# 06-Front_Panel_SFP_2.net
KiCad netlist of a schematic drawn in Altium Designer
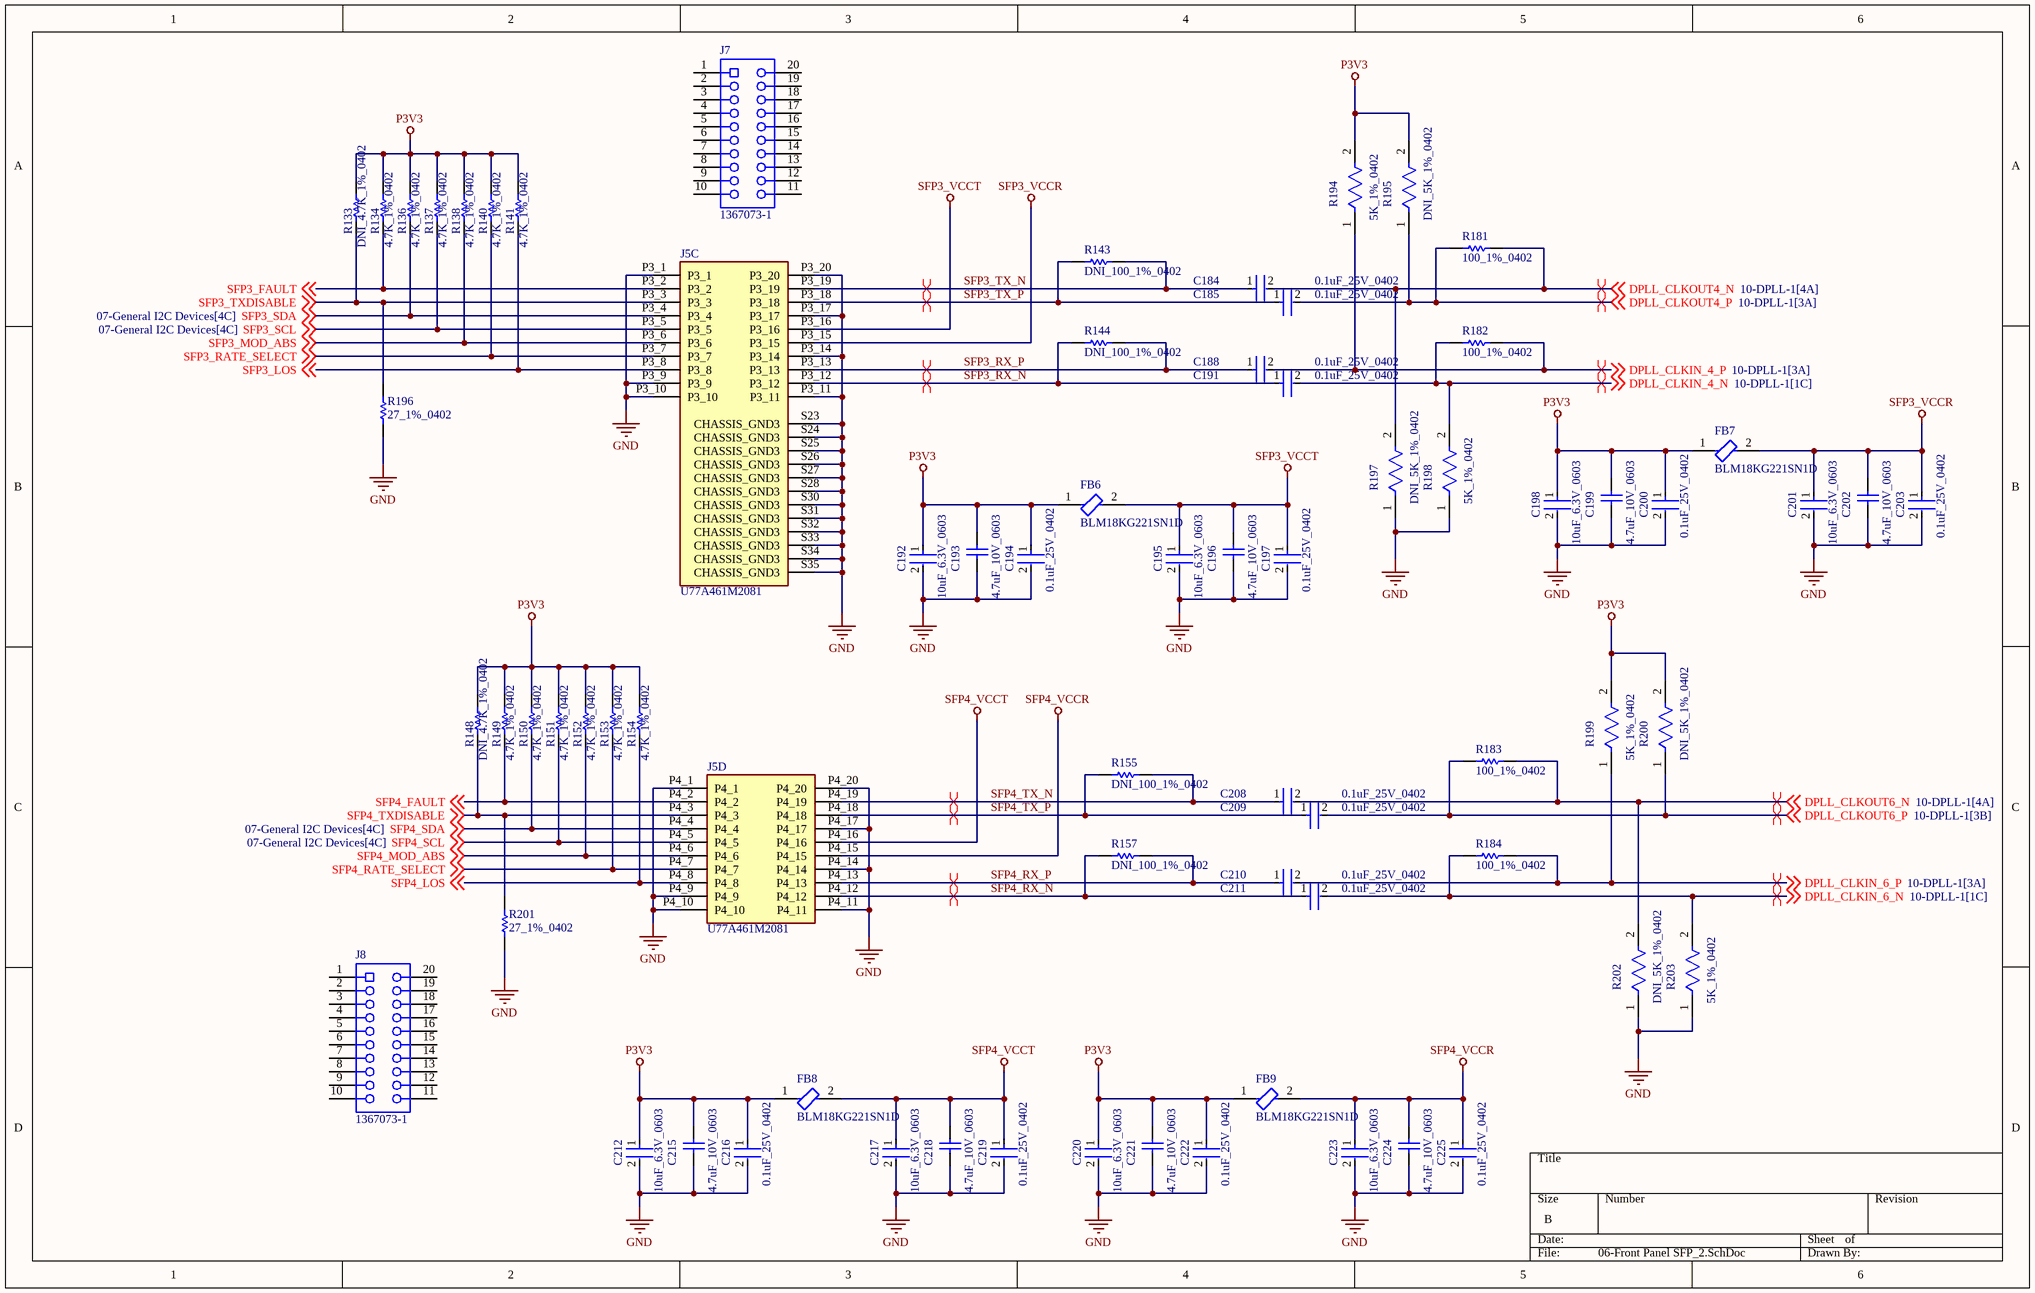
[diagram p0: 06-Front Panel SFP_2.SchDoc]

(export (version "E")
  (design (tool "Eeschema 10.0.6"))
  (components
    (comp (ref "C184")
      (value "0.1uF_25V_0402")
      (footprint "FP-0402-L_1_0_1-W_0_5_0_1-IPC_C")
      (description "General Purpose Ceramic Capacitor, 0402, 100nF, 10%, X7R, 15%, 25V")
      (fields (field (name "VOLTAGE") "25V") (field (name "TOLERANCE") "10%"))
      (libsource (lib "Altium Content Vault") (part "b4654b650e69147ec39a6b967a45e02"))
    )
    (comp (ref "C185")
      (value "0.1uF_25V_0402")
      (footprint "FP-0402-L_1_0_1-W_0_5_0_1-IPC_C")
      (description "General Purpose Ceramic Capacitor, 0402, 100nF, 10%, X7R, 15%, 25V")
      (fields (field (name "VOLTAGE") "25V") (field (name "TOLERANCE") "10%"))
      (libsource (lib "Altium Content Vault") (part "b4654b650e69147ec39a6b967a45e02"))
    )
    (comp (ref "C188")
      (value "0.1uF_25V_0402")
      (footprint "FP-0402-L_1_0_1-W_0_5_0_1-IPC_C")
      (description "General Purpose Ceramic Capacitor, 0402, 100nF, 10%, X7R, 15%, 25V")
      (fields (field (name "VOLTAGE") "25V") (field (name "TOLERANCE") "10%"))
      (libsource (lib "Altium Content Vault") (part "b4654b650e69147ec39a6b967a45e02"))
    )
    (comp (ref "C191")
      (value "0.1uF_25V_0402")
      (footprint "FP-0402-L_1_0_1-W_0_5_0_1-IPC_C")
      (description "General Purpose Ceramic Capacitor, 0402, 100nF, 10%, X7R, 15%, 25V")
      (fields (field (name "VOLTAGE") "25V") (field (name "TOLERANCE") "10%"))
      (libsource (lib "Altium Content Vault") (part "b4654b650e69147ec39a6b967a45e02"))
    )
    (comp (ref "C192")
      (value "10uF_6.3V_0603")
      (footprint "FP-C0603C106M9PACTU-MFG")
      (description "CAP CER 10UF 6.3V X5R 0603")
      (fields
        (field (name "MANUFACTURER PART NUMBER") "C0603C106M9PACTU")
        (field (name "MANUFACTURER") "Kemet")
      )
      (libsource (lib "Altium Content Vault") (part "b4654b650e69147ec39a6b967a45e02"))
    )
    (comp (ref "C193")
      (value "4.7uF_10V_0603")
      (footprint "CAPC1608X87X35NL15T15")
      (fields (field (name "PART NUMBER") "C0603C475K8PACTU") (field (name "MANUFACTURER") "Kemet"))
      (libsource (lib "Altium Content Vault") (part "CAP"))
    )
    (comp (ref "C194")
      (value "0.1uF_25V_0402")
      (footprint "FP-0402-L_1_0_1-W_0_5_0_1-IPC_C")
      (description "General Purpose Ceramic Capacitor, 0402, 100nF, 10%, X7R, 15%, 25V")
      (fields (field (name "VOLTAGE") "25V") (field (name "TOLERANCE") "10%"))
      (libsource (lib "Altium Content Vault") (part "b4654b650e69147ec39a6b967a45e02"))
    )
    (comp (ref "C195")
      (value "10uF_6.3V_0603")
      (footprint "FP-C0603C106M9PACTU-MFG")
      (description "CAP CER 10UF 6.3V X5R 0603")
      (fields
        (field (name "MANUFACTURER PART NUMBER") "C0603C106M9PACTU")
        (field (name "MANUFACTURER") "Kemet")
      )
      (libsource (lib "Altium Content Vault") (part "b4654b650e69147ec39a6b967a45e02"))
    )
    (comp (ref "C196")
      (value "4.7uF_10V_0603")
      (footprint "CAPC1608X87X35NL15T15")
      (fields (field (name "PART NUMBER") "C0603C475K8PACTU") (field (name "MANUFACTURER") "Kemet"))
      (libsource (lib "Altium Content Vault") (part "CAP"))
    )
    (comp (ref "C197")
      (value "0.1uF_25V_0402")
      (footprint "FP-0402-L_1_0_1-W_0_5_0_1-IPC_C")
      (description "General Purpose Ceramic Capacitor, 0402, 100nF, 10%, X7R, 15%, 25V")
      (fields (field (name "VOLTAGE") "25V") (field (name "TOLERANCE") "10%"))
      (libsource (lib "Altium Content Vault") (part "b4654b650e69147ec39a6b967a45e02"))
    )
    (comp (ref "C198")
      (value "10uF_6.3V_0603")
      (footprint "FP-C0603C106M9PACTU-MFG")
      (description "CAP CER 10UF 6.3V X5R 0603")
      (fields
        (field (name "MANUFACTURER PART NUMBER") "C0603C106M9PACTU")
        (field (name "MANUFACTURER") "Kemet")
      )
      (libsource (lib "Altium Content Vault") (part "b4654b650e69147ec39a6b967a45e02"))
    )
    (comp (ref "C199")
      (value "4.7uF_10V_0603")
      (footprint "CAPC1608X87X35NL15T15")
      (fields (field (name "PART NUMBER") "C0603C475K8PACTU") (field (name "MANUFACTURER") "Kemet"))
      (libsource (lib "Altium Content Vault") (part "CAP"))
    )
    (comp (ref "C200")
      (value "0.1uF_25V_0402")
      (footprint "FP-0402-L_1_0_1-W_0_5_0_1-IPC_C")
      (description "General Purpose Ceramic Capacitor, 0402, 100nF, 10%, X7R, 15%, 25V")
      (fields (field (name "VOLTAGE") "25V") (field (name "TOLERANCE") "10%"))
      (libsource (lib "Altium Content Vault") (part "b4654b650e69147ec39a6b967a45e02"))
    )
    (comp (ref "C201")
      (value "10uF_6.3V_0603")
      (footprint "FP-C0603C106M9PACTU-MFG")
      (description "CAP CER 10UF 6.3V X5R 0603")
      (fields
        (field (name "MANUFACTURER PART NUMBER") "C0603C106M9PACTU")
        (field (name "MANUFACTURER") "Kemet")
      )
      (libsource (lib "Altium Content Vault") (part "b4654b650e69147ec39a6b967a45e02"))
    )
    (comp (ref "C202")
      (value "4.7uF_10V_0603")
      (footprint "CAPC1608X87X35NL15T15")
      (fields (field (name "PART NUMBER") "C0603C475K8PACTU") (field (name "MANUFACTURER") "Kemet"))
      (libsource (lib "Altium Content Vault") (part "CAP"))
    )
    (comp (ref "C203")
      (value "0.1uF_25V_0402")
      (footprint "FP-0402-L_1_0_1-W_0_5_0_1-IPC_C")
      (description "General Purpose Ceramic Capacitor, 0402, 100nF, 10%, X7R, 15%, 25V")
      (fields (field (name "VOLTAGE") "25V") (field (name "TOLERANCE") "10%"))
      (libsource (lib "Altium Content Vault") (part "b4654b650e69147ec39a6b967a45e02"))
    )
    (comp (ref "C208")
      (value "0.1uF_25V_0402")
      (footprint "FP-0402-L_1_0_1-W_0_5_0_1-IPC_C")
      (description "General Purpose Ceramic Capacitor, 0402, 100nF, 10%, X7R, 15%, 25V")
      (fields (field (name "VOLTAGE") "25V") (field (name "TOLERANCE") "10%"))
      (libsource (lib "Altium Content Vault") (part "b4654b650e69147ec39a6b967a45e02"))
    )
    (comp (ref "C209")
      (value "0.1uF_25V_0402")
      (footprint "FP-0402-L_1_0_1-W_0_5_0_1-IPC_C")
      (description "General Purpose Ceramic Capacitor, 0402, 100nF, 10%, X7R, 15%, 25V")
      (fields (field (name "VOLTAGE") "25V") (field (name "TOLERANCE") "10%"))
      (libsource (lib "Altium Content Vault") (part "b4654b650e69147ec39a6b967a45e02"))
    )
    (comp (ref "C210")
      (value "0.1uF_25V_0402")
      (footprint "FP-0402-L_1_0_1-W_0_5_0_1-IPC_C")
      (description "General Purpose Ceramic Capacitor, 0402, 100nF, 10%, X7R, 15%, 25V")
      (fields (field (name "VOLTAGE") "25V") (field (name "TOLERANCE") "10%"))
      (libsource (lib "Altium Content Vault") (part "b4654b650e69147ec39a6b967a45e02"))
    )
    (comp (ref "C211")
      (value "0.1uF_25V_0402")
      (footprint "FP-0402-L_1_0_1-W_0_5_0_1-IPC_C")
      (description "General Purpose Ceramic Capacitor, 0402, 100nF, 10%, X7R, 15%, 25V")
      (fields (field (name "VOLTAGE") "25V") (field (name "TOLERANCE") "10%"))
      (libsource (lib "Altium Content Vault") (part "b4654b650e69147ec39a6b967a45e02"))
    )
    (comp (ref "C212")
      (value "10uF_6.3V_0603")
      (footprint "FP-C0603C106M9PACTU-MFG")
      (description "CAP CER 10UF 6.3V X5R 0603")
      (fields
        (field (name "MANUFACTURER PART NUMBER") "C0603C106M9PACTU")
        (field (name "MANUFACTURER") "Kemet")
      )
      (libsource (lib "Altium Content Vault") (part "b4654b650e69147ec39a6b967a45e02"))
    )
    (comp (ref "C215")
      (value "4.7uF_10V_0603")
      (footprint "CAPC1608X87X35NL15T15")
      (fields (field (name "PART NUMBER") "C0603C475K8PACTU") (field (name "MANUFACTURER") "Kemet"))
      (libsource (lib "Altium Content Vault") (part "CAP"))
    )
    (comp (ref "C216")
      (value "0.1uF_25V_0402")
      (footprint "FP-0402-L_1_0_1-W_0_5_0_1-IPC_C")
      (description "General Purpose Ceramic Capacitor, 0402, 100nF, 10%, X7R, 15%, 25V")
      (fields (field (name "VOLTAGE") "25V") (field (name "TOLERANCE") "10%"))
      (libsource (lib "Altium Content Vault") (part "b4654b650e69147ec39a6b967a45e02"))
    )
    (comp (ref "C217")
      (value "10uF_6.3V_0603")
      (footprint "FP-C0603C106M9PACTU-MFG")
      (description "CAP CER 10UF 6.3V X5R 0603")
      (fields
        (field (name "MANUFACTURER PART NUMBER") "C0603C106M9PACTU")
        (field (name "MANUFACTURER") "Kemet")
      )
      (libsource (lib "Altium Content Vault") (part "b4654b650e69147ec39a6b967a45e02"))
    )
    (comp (ref "C218")
      (value "4.7uF_10V_0603")
      (footprint "CAPC1608X87X35NL15T15")
      (fields (field (name "PART NUMBER") "C0603C475K8PACTU") (field (name "MANUFACTURER") "Kemet"))
      (libsource (lib "Altium Content Vault") (part "CAP"))
    )
    (comp (ref "C219")
      (value "0.1uF_25V_0402")
      (footprint "FP-0402-L_1_0_1-W_0_5_0_1-IPC_C")
      (description "General Purpose Ceramic Capacitor, 0402, 100nF, 10%, X7R, 15%, 25V")
      (fields (field (name "VOLTAGE") "25V") (field (name "TOLERANCE") "10%"))
      (libsource (lib "Altium Content Vault") (part "b4654b650e69147ec39a6b967a45e02"))
    )
    (comp (ref "C220")
      (value "10uF_6.3V_0603")
      (footprint "FP-C0603C106M9PACTU-MFG")
      (description "CAP CER 10UF 6.3V X5R 0603")
      (fields
        (field (name "MANUFACTURER PART NUMBER") "C0603C106M9PACTU")
        (field (name "MANUFACTURER") "Kemet")
      )
      (libsource (lib "Altium Content Vault") (part "b4654b650e69147ec39a6b967a45e02"))
    )
    (comp (ref "C221")
      (value "4.7uF_10V_0603")
      (footprint "CAPC1608X87X35NL15T15")
      (fields (field (name "PART NUMBER") "C0603C475K8PACTU") (field (name "MANUFACTURER") "Kemet"))
      (libsource (lib "Altium Content Vault") (part "CAP"))
    )
    (comp (ref "C222")
      (value "0.1uF_25V_0402")
      (footprint "FP-0402-L_1_0_1-W_0_5_0_1-IPC_C")
      (description "General Purpose Ceramic Capacitor, 0402, 100nF, 10%, X7R, 15%, 25V")
      (fields (field (name "VOLTAGE") "25V") (field (name "TOLERANCE") "10%"))
      (libsource (lib "Altium Content Vault") (part "b4654b650e69147ec39a6b967a45e02"))
    )
    (comp (ref "C223")
      (value "10uF_6.3V_0603")
      (footprint "FP-C0603C106M9PACTU-MFG")
      (description "CAP CER 10UF 6.3V X5R 0603")
      (fields
        (field (name "MANUFACTURER PART NUMBER") "C0603C106M9PACTU")
        (field (name "MANUFACTURER") "Kemet")
      )
      (libsource (lib "Altium Content Vault") (part "b4654b650e69147ec39a6b967a45e02"))
    )
    (comp (ref "C224")
      (value "4.7uF_10V_0603")
      (footprint "CAPC1608X87X35NL15T15")
      (fields (field (name "PART NUMBER") "C0603C475K8PACTU") (field (name "MANUFACTURER") "Kemet"))
      (libsource (lib "Altium Content Vault") (part "CAP"))
    )
    (comp (ref "C225")
      (value "0.1uF_25V_0402")
      (footprint "FP-0402-L_1_0_1-W_0_5_0_1-IPC_C")
      (description "General Purpose Ceramic Capacitor, 0402, 100nF, 10%, X7R, 15%, 25V")
      (fields (field (name "VOLTAGE") "25V") (field (name "TOLERANCE") "10%"))
      (libsource (lib "Altium Content Vault") (part "b4654b650e69147ec39a6b967a45e02"))
    )
    (comp (ref "FB6")
      (value "BLM18KG221SN1D")
      (footprint "FP-BLM18-0_15-t0_8-IPC_B")
      (description "Chip Ferrite Bead, 0603, 220Ω @ 100MHz, 0.05Ω, 25%, 2.2A")
      (fields (field (name "TOLERANCE") "25%"))
      (libsource (lib "Altium Content Vault") (part "5f30dd21d616792df468990f7003faa"))
    )
    (comp (ref "FB7")
      (value "BLM18KG221SN1D")
      (footprint "FP-BLM18-0_15-t0_8-IPC_B")
      (description "Chip Ferrite Bead, 0603, 220Ω @ 100MHz, 0.05Ω, 25%, 2.2A")
      (fields (field (name "TOLERANCE") "25%"))
      (libsource (lib "Altium Content Vault") (part "5f30dd21d616792df468990f7003faa"))
    )
    (comp (ref "FB8")
      (value "BLM18KG221SN1D")
      (footprint "FP-BLM18-0_15-t0_8-IPC_B")
      (description "Chip Ferrite Bead, 0603, 220Ω @ 100MHz, 0.05Ω, 25%, 2.2A")
      (fields (field (name "TOLERANCE") "25%"))
      (libsource (lib "Altium Content Vault") (part "5f30dd21d616792df468990f7003faa"))
    )
    (comp (ref "FB9")
      (value "BLM18KG221SN1D")
      (footprint "FP-BLM18-0_15-t0_8-IPC_B")
      (description "Chip Ferrite Bead, 0603, 220Ω @ 100MHz, 0.05Ω, 25%, 2.2A")
      (fields (field (name "TOLERANCE") "25%"))
      (libsource (lib "Altium Content Vault") (part "5f30dd21d616792df468990f7003faa"))
    )
    (comp (ref "J5")
      (value "U77A461M2081")
      (footprint "AMPHENOL_U77A461M2081")
      (fields (field (name "MF") "AMPHENOL ICC / FCI"))
      (libsource (lib "U77A461M2081") (part "U77A461M2081"))
    )
    (comp (ref "J7")
      (value "1367073-1")
      (footprint "TECO-1367073-1_V")
      (fields (field (name "MANUFACTURER") "TE Connectivity"))
      (libsource (lib "Altium Content Vault") (part "CN-2P-F-R20_B"))
    )
    (comp (ref "J8")
      (value "1367073-1")
      (footprint "TECO-1367073-1_V")
      (fields (field (name "MANUFACTURER") "TE Connectivity"))
      (libsource (lib "Altium Content Vault") (part "CN-2P-F-R20_B"))
    )
    (comp (ref "R133")
      (value "DNI_4.7K_1%_0402")
      (footprint "RESC1005X40X25NL10T10")
      (fields (field (name "MANUFACTURER") "Bourns") (field (name "PART NUMBER") "CR0402-FX-4701GLF"))
      (libsource (lib "Altium Content Vault") (part "RES"))
    )
    (comp (ref "R134")
      (value "4.7K_1%_0402")
      (footprint "RESC1005X40X25NL10T10")
      (fields (field (name "MANUFACTURER") "Bourns") (field (name "PART NUMBER") "CR0402-FX-4701GLF"))
      (libsource (lib "Altium Content Vault") (part "RES"))
    )
    (comp (ref "R136")
      (value "4.7K_1%_0402")
      (footprint "RESC1005X40X25NL10T10")
      (fields (field (name "MANUFACTURER") "Bourns") (field (name "PART NUMBER") "CR0402-FX-4701GLF"))
      (libsource (lib "Altium Content Vault") (part "RES"))
    )
    (comp (ref "R137")
      (value "4.7K_1%_0402")
      (footprint "RESC1005X40X25NL10T10")
      (fields (field (name "MANUFACTURER") "Bourns") (field (name "PART NUMBER") "CR0402-FX-4701GLF"))
      (libsource (lib "Altium Content Vault") (part "RES"))
    )
    (comp (ref "R138")
      (value "4.7K_1%_0402")
      (footprint "RESC1005X40X25NL10T10")
      (fields (field (name "MANUFACTURER") "Bourns") (field (name "PART NUMBER") "CR0402-FX-4701GLF"))
      (libsource (lib "Altium Content Vault") (part "RES"))
    )
    (comp (ref "R140")
      (value "4.7K_1%_0402")
      (footprint "RESC1005X40X25NL10T10")
      (fields (field (name "MANUFACTURER") "Bourns") (field (name "PART NUMBER") "CR0402-FX-4701GLF"))
      (libsource (lib "Altium Content Vault") (part "RES"))
    )
    (comp (ref "R141")
      (value "4.7K_1%_0402")
      (footprint "RESC1005X40X25NL10T10")
      (fields (field (name "MANUFACTURER") "Bourns") (field (name "PART NUMBER") "CR0402-FX-4701GLF"))
      (libsource (lib "Altium Content Vault") (part "RES"))
    )
    (comp (ref "R143")
      (value "DNI_100_1%_0402")
      (footprint "RESC1005X40X25NL05T10")
      (fields (field (name "MANUFACTURER") "Yageo") (field (name "PART NUMBER") "RC0402FR-13100RL"))
      (libsource (lib "Altium Content Vault") (part "RES"))
    )
    (comp (ref "R144")
      (value "DNI_100_1%_0402")
      (footprint "RESC1005X40X25NL05T10")
      (fields (field (name "MANUFACTURER") "Yageo") (field (name "PART NUMBER") "RC0402FR-13100RL"))
      (libsource (lib "Altium Content Vault") (part "RES"))
    )
    (comp (ref "R148")
      (value "DNI_4.7K_1%_0402")
      (footprint "RESC1005X40X25NL10T10")
      (fields (field (name "MANUFACTURER") "Bourns") (field (name "PART NUMBER") "CR0402-FX-4701GLF"))
      (libsource (lib "Altium Content Vault") (part "RES"))
    )
    (comp (ref "R149")
      (value "4.7K_1%_0402")
      (footprint "RESC1005X40X25NL10T10")
      (fields (field (name "MANUFACTURER") "Bourns") (field (name "PART NUMBER") "CR0402-FX-4701GLF"))
      (libsource (lib "Altium Content Vault") (part "RES"))
    )
    (comp (ref "R150")
      (value "4.7K_1%_0402")
      (footprint "RESC1005X40X25NL10T10")
      (fields (field (name "MANUFACTURER") "Bourns") (field (name "PART NUMBER") "CR0402-FX-4701GLF"))
      (libsource (lib "Altium Content Vault") (part "RES"))
    )
    (comp (ref "R151")
      (value "4.7K_1%_0402")
      (footprint "RESC1005X40X25NL10T10")
      (fields (field (name "MANUFACTURER") "Bourns") (field (name "PART NUMBER") "CR0402-FX-4701GLF"))
      (libsource (lib "Altium Content Vault") (part "RES"))
    )
    (comp (ref "R152")
      (value "4.7K_1%_0402")
      (footprint "RESC1005X40X25NL10T10")
      (fields (field (name "MANUFACTURER") "Bourns") (field (name "PART NUMBER") "CR0402-FX-4701GLF"))
      (libsource (lib "Altium Content Vault") (part "RES"))
    )
    (comp (ref "R153")
      (value "4.7K_1%_0402")
      (footprint "RESC1005X40X25NL10T10")
      (fields (field (name "MANUFACTURER") "Bourns") (field (name "PART NUMBER") "CR0402-FX-4701GLF"))
      (libsource (lib "Altium Content Vault") (part "RES"))
    )
    (comp (ref "R154")
      (value "4.7K_1%_0402")
      (footprint "RESC1005X40X25NL10T10")
      (fields (field (name "MANUFACTURER") "Bourns") (field (name "PART NUMBER") "CR0402-FX-4701GLF"))
      (libsource (lib "Altium Content Vault") (part "RES"))
    )
    (comp (ref "R155")
      (value "DNI_100_1%_0402")
      (footprint "RESC1005X40X25NL05T10")
      (fields (field (name "MANUFACTURER") "Yageo") (field (name "PART NUMBER") "RC0402FR-13100RL"))
      (libsource (lib "Altium Content Vault") (part "RES"))
    )
    (comp (ref "R157")
      (value "DNI_100_1%_0402")
      (footprint "RESC1005X40X25NL05T10")
      (fields (field (name "MANUFACTURER") "Yageo") (field (name "PART NUMBER") "RC0402FR-13100RL"))
      (libsource (lib "Altium Content Vault") (part "RES"))
    )
    (comp (ref "R181")
      (value "100_1%_0402")
      (footprint "RESC1005X40X25NL05T10")
      (fields (field (name "MANUFACTURER") "Yageo") (field (name "PART NUMBER") "RC0402FR-13100RL"))
      (libsource (lib "Altium Content Vault") (part "RES"))
    )
    (comp (ref "R182")
      (value "100_1%_0402")
      (footprint "RESC1005X40X25NL05T10")
      (fields (field (name "MANUFACTURER") "Yageo") (field (name "PART NUMBER") "RC0402FR-13100RL"))
      (libsource (lib "Altium Content Vault") (part "RES"))
    )
    (comp (ref "R183")
      (value "100_1%_0402")
      (footprint "RESC1005X40X25NL05T10")
      (fields (field (name "MANUFACTURER") "Yageo") (field (name "PART NUMBER") "RC0402FR-13100RL"))
      (libsource (lib "Altium Content Vault") (part "RES"))
    )
    (comp (ref "R184")
      (value "100_1%_0402")
      (footprint "RESC1005X40X25NL05T10")
      (fields (field (name "MANUFACTURER") "Yageo") (field (name "PART NUMBER") "RC0402FR-13100RL"))
      (libsource (lib "Altium Content Vault") (part "RES"))
    )
    (comp (ref "R194")
      (value "5K_1%_0402")
      (footprint "FP-RC0402-MFG")
      (description "RES SMD 5K OHM 1% 1/16W 0402")
      (fields (field (name "MANUFACTURER") "Yageo") (field (name "TOLERANCE") "1%"))
      (libsource (lib "Altium Content Vault") (part "1029c3af85768c4190bb7ad29bc67b5"))
    )
    (comp (ref "R195")
      (value "DNI_5K_1%_0402")
      (footprint "FP-RC0402-MFG")
      (description "RES SMD 5K OHM 1% 1/16W 0402")
      (fields (field (name "MANUFACTURER") "Yageo") (field (name "TOLERANCE") "1%"))
      (libsource (lib "Altium Content Vault") (part "1029c3af85768c4190bb7ad29bc67b5"))
    )
    (comp (ref "R196")
      (value "27_1%_0402")
      (footprint "RESC1005X40X25NL05T05")
      (fields (field (name "PART NUMBER") "CRCW040227R0FKED") (field (name "MANUFACTURER") "Vishay Dale"))
      (libsource (lib "Altium Content Vault") (part "RES"))
    )
    (comp (ref "R197")
      (value "DNI_5K_1%_0402")
      (footprint "FP-RC0402-MFG")
      (description "RES SMD 5K OHM 1% 1/16W 0402")
      (fields (field (name "MANUFACTURER") "Yageo") (field (name "TOLERANCE") "1%"))
      (libsource (lib "Altium Content Vault") (part "1029c3af85768c4190bb7ad29bc67b5"))
    )
    (comp (ref "R198")
      (value "5K_1%_0402")
      (footprint "FP-RC0402-MFG")
      (description "RES SMD 5K OHM 1% 1/16W 0402")
      (fields (field (name "MANUFACTURER") "Yageo") (field (name "TOLERANCE") "1%"))
      (libsource (lib "Altium Content Vault") (part "1029c3af85768c4190bb7ad29bc67b5"))
    )
    (comp (ref "R199")
      (value "5K_1%_0402")
      (footprint "FP-RC0402-MFG")
      (description "RES SMD 5K OHM 1% 1/16W 0402")
      (fields (field (name "MANUFACTURER") "Yageo") (field (name "TOLERANCE") "1%"))
      (libsource (lib "Altium Content Vault") (part "1029c3af85768c4190bb7ad29bc67b5"))
    )
    (comp (ref "R200")
      (value "DNI_5K_1%_0402")
      (footprint "FP-RC0402-MFG")
      (description "RES SMD 5K OHM 1% 1/16W 0402")
      (fields (field (name "MANUFACTURER") "Yageo") (field (name "TOLERANCE") "1%"))
      (libsource (lib "Altium Content Vault") (part "1029c3af85768c4190bb7ad29bc67b5"))
    )
    (comp (ref "R201")
      (value "27_1%_0402")
      (footprint "RESC1005X40X25NL05T05")
      (fields (field (name "PART NUMBER") "CRCW040227R0FKED") (field (name "MANUFACTURER") "Vishay Dale"))
      (libsource (lib "Altium Content Vault") (part "RES"))
    )
    (comp (ref "R202")
      (value "DNI_5K_1%_0402")
      (footprint "FP-RC0402-MFG")
      (description "RES SMD 5K OHM 1% 1/16W 0402")
      (fields (field (name "MANUFACTURER") "Yageo") (field (name "TOLERANCE") "1%"))
      (libsource (lib "Altium Content Vault") (part "1029c3af85768c4190bb7ad29bc67b5"))
    )
    (comp (ref "R203")
      (value "5K_1%_0402")
      (footprint "FP-RC0402-MFG")
      (description "RES SMD 5K OHM 1% 1/16W 0402")
      (fields (field (name "MANUFACTURER") "Yageo") (field (name "TOLERANCE") "1%"))
      (libsource (lib "Altium Content Vault") (part "1029c3af85768c4190bb7ad29bc67b5"))
    )
  )
  (nets
    (net (code "1") (name "/SFP3_RX_N") (class "Default")
      (node (ref "C191") (pin "1") (pinfunction "1_1") (pintype "passive"))
      (node (ref "J5") (pin "P3_12") (pinfunction "P3_12_P3_12") (pintype "passive"))
      (node (ref "R144") (pin "1") (pinfunction "1_1") (pintype "passive"))
    )
    (net (code "2") (name "/SFP3_RX_P") (class "Default")
      (node (ref "C188") (pin "1") (pinfunction "1_1") (pintype "passive"))
      (node (ref "J5") (pin "P3_13") (pinfunction "P3_13_P3_13") (pintype "passive"))
      (node (ref "R144") (pin "2") (pinfunction "2_2") (pintype "passive"))
    )
    (net (code "3") (name "/SFP3_TX_N") (class "Default")
      (node (ref "C184") (pin "1") (pinfunction "1_1") (pintype "passive"))
      (node (ref "J5") (pin "P3_19") (pinfunction "P3_19_P3_19") (pintype "passive"))
      (node (ref "R143") (pin "2") (pinfunction "2_2") (pintype "passive"))
    )
    (net (code "4") (name "/SFP3_TX_P") (class "Default")
      (node (ref "C185") (pin "1") (pinfunction "1_1") (pintype "passive"))
      (node (ref "J5") (pin "P3_18") (pinfunction "P3_18_P3_18") (pintype "passive"))
      (node (ref "R143") (pin "1") (pinfunction "1_1") (pintype "passive"))
    )
    (net (code "5") (name "/SFP4_RX_N") (class "Default")
      (node (ref "C211") (pin "1") (pinfunction "1_1") (pintype "passive"))
      (node (ref "J5") (pin "P4_12") (pinfunction "P4_12_P4_12") (pintype "passive"))
      (node (ref "R157") (pin "1") (pinfunction "1_1") (pintype "passive"))
    )
    (net (code "6") (name "/SFP4_RX_P") (class "Default")
      (node (ref "C210") (pin "1") (pinfunction "1_1") (pintype "passive"))
      (node (ref "J5") (pin "P4_13") (pinfunction "P4_13_P4_13") (pintype "passive"))
      (node (ref "R157") (pin "2") (pinfunction "2_2") (pintype "passive"))
    )
    (net (code "7") (name "/SFP4_TX_N") (class "Default")
      (node (ref "C208") (pin "1") (pinfunction "1_1") (pintype "passive"))
      (node (ref "J5") (pin "P4_19") (pinfunction "P4_19_P4_19") (pintype "passive"))
      (node (ref "R155") (pin "2") (pinfunction "2_2") (pintype "passive"))
    )
    (net (code "8") (name "/SFP4_TX_P") (class "Default")
      (node (ref "C209") (pin "1") (pinfunction "1_1") (pintype "passive"))
      (node (ref "J5") (pin "P4_18") (pinfunction "P4_18_P4_18") (pintype "passive"))
      (node (ref "R155") (pin "1") (pinfunction "1_1") (pintype "passive"))
    )
    (net (code "9") (name "DPLL_CLKIN_4_N") (class "Default")
      (node (ref "C191") (pin "2") (pinfunction "2_2") (pintype "passive"))
      (node (ref "R182") (pin "1") (pinfunction "1_1") (pintype "passive"))
      (node (ref "R198") (pin "2") (pinfunction "2_2") (pintype "passive"))
    )
    (net (code "10") (name "DPLL_CLKIN_4_P") (class "Default")
      (node (ref "C188") (pin "2") (pinfunction "2_2") (pintype "passive"))
      (node (ref "R182") (pin "2") (pinfunction "2_2") (pintype "passive"))
      (node (ref "R194") (pin "1") (pinfunction "1_1") (pintype "passive"))
    )
    (net (code "11") (name "DPLL_CLKIN_6_N") (class "Default")
      (node (ref "C211") (pin "2") (pinfunction "2_2") (pintype "passive"))
      (node (ref "R184") (pin "1") (pinfunction "1_1") (pintype "passive"))
      (node (ref "R203") (pin "2") (pinfunction "2_2") (pintype "passive"))
    )
    (net (code "12") (name "DPLL_CLKIN_6_P") (class "Default")
      (node (ref "C210") (pin "2") (pinfunction "2_2") (pintype "passive"))
      (node (ref "R184") (pin "2") (pinfunction "2_2") (pintype "passive"))
      (node (ref "R199") (pin "1") (pinfunction "1_1") (pintype "passive"))
    )
    (net (code "13") (name "DPLL_CLKOUT4_N") (class "Default")
      (node (ref "C184") (pin "2") (pinfunction "2_2") (pintype "passive"))
      (node (ref "R181") (pin "2") (pinfunction "2_2") (pintype "passive"))
      (node (ref "R197") (pin "2") (pinfunction "2_2") (pintype "passive"))
    )
    (net (code "14") (name "DPLL_CLKOUT4_P") (class "Default")
      (node (ref "C185") (pin "2") (pinfunction "2_2") (pintype "passive"))
      (node (ref "R181") (pin "1") (pinfunction "1_1") (pintype "passive"))
      (node (ref "R195") (pin "1") (pinfunction "1_1") (pintype "passive"))
    )
    (net (code "15") (name "DPLL_CLKOUT6_N") (class "Default")
      (node (ref "C208") (pin "2") (pinfunction "2_2") (pintype "passive"))
      (node (ref "R183") (pin "2") (pinfunction "2_2") (pintype "passive"))
      (node (ref "R202") (pin "2") (pinfunction "2_2") (pintype "passive"))
    )
    (net (code "16") (name "DPLL_CLKOUT6_P") (class "Default")
      (node (ref "C209") (pin "2") (pinfunction "2_2") (pintype "passive"))
      (node (ref "R183") (pin "1") (pinfunction "1_1") (pintype "passive"))
      (node (ref "R200") (pin "1") (pinfunction "1_1") (pintype "passive"))
    )
    (net (code "17") (name "GND") (class "Default")
      (node (ref "C192") (pin "2") (pinfunction "2_2") (pintype "passive"))
      (node (ref "C193") (pin "1") (pinfunction "1_1") (pintype "passive"))
      (node (ref "C194") (pin "2") (pinfunction "2_2") (pintype "passive"))
      (node (ref "C195") (pin "2") (pinfunction "2_2") (pintype "passive"))
      (node (ref "C196") (pin "1") (pinfunction "1_1") (pintype "passive"))
      (node (ref "C197") (pin "2") (pinfunction "2_2") (pintype "passive"))
      (node (ref "C198") (pin "2") (pinfunction "2_2") (pintype "passive"))
      (node (ref "C199") (pin "1") (pinfunction "1_1") (pintype "passive"))
      (node (ref "C200") (pin "2") (pinfunction "2_2") (pintype "passive"))
      (node (ref "C201") (pin "2") (pinfunction "2_2") (pintype "passive"))
      (node (ref "C202") (pin "1") (pinfunction "1_1") (pintype "passive"))
      (node (ref "C203") (pin "2") (pinfunction "2_2") (pintype "passive"))
      (node (ref "C212") (pin "2") (pinfunction "2_2") (pintype "passive"))
      (node (ref "C215") (pin "1") (pinfunction "1_1") (pintype "passive"))
      (node (ref "C216") (pin "2") (pinfunction "2_2") (pintype "passive"))
      (node (ref "C217") (pin "2") (pinfunction "2_2") (pintype "passive"))
      (node (ref "C218") (pin "1") (pinfunction "1_1") (pintype "passive"))
      (node (ref "C219") (pin "2") (pinfunction "2_2") (pintype "passive"))
      (node (ref "C220") (pin "2") (pinfunction "2_2") (pintype "passive"))
      (node (ref "C221") (pin "1") (pinfunction "1_1") (pintype "passive"))
      (node (ref "C222") (pin "2") (pinfunction "2_2") (pintype "passive"))
      (node (ref "C223") (pin "2") (pinfunction "2_2") (pintype "passive"))
      (node (ref "C224") (pin "1") (pinfunction "1_1") (pintype "passive"))
      (node (ref "C225") (pin "2") (pinfunction "2_2") (pintype "passive"))
      (node (ref "J5") (pin "P3_1") (pinfunction "P3_1_P3_1") (pintype "passive"))
      (node (ref "J5") (pin "P3_10") (pinfunction "P3_10_P3_10") (pintype "passive"))
      (node (ref "J5") (pin "P3_11") (pinfunction "P3_11_P3_11") (pintype "passive"))
      (node (ref "J5") (pin "P3_14") (pinfunction "P3_14_P3_14") (pintype "passive"))
      (node (ref "J5") (pin "P3_17") (pinfunction "P3_17_P3_17") (pintype "passive"))
      (node (ref "J5") (pin "P3_20") (pinfunction "P3_20_P3_20") (pintype "passive"))
      (node (ref "J5") (pin "P3_9") (pinfunction "P3_9_P3_9") (pintype "passive"))
      (node (ref "J5") (pin "P4_1") (pinfunction "P4_1_P4_1") (pintype "passive"))
      (node (ref "J5") (pin "P4_10") (pinfunction "P4_10_P4_10") (pintype "passive"))
      (node (ref "J5") (pin "P4_11") (pinfunction "P4_11_P4_11") (pintype "passive"))
      (node (ref "J5") (pin "P4_14") (pinfunction "P4_14_P4_14") (pintype "passive"))
      (node (ref "J5") (pin "P4_17") (pinfunction "P4_17_P4_17") (pintype "passive"))
      (node (ref "J5") (pin "P4_20") (pinfunction "P4_20_P4_20") (pintype "passive"))
      (node (ref "J5") (pin "P4_9") (pinfunction "P4_9_P4_9") (pintype "passive"))
      (node (ref "J5") (pin "S23") (pinfunction "CHASSIS_GND3_S23") (pintype "passive"))
      (node (ref "J5") (pin "S24") (pinfunction "CHASSIS_GND3_S24") (pintype "passive"))
      (node (ref "J5") (pin "S25") (pinfunction "CHASSIS_GND3_S25") (pintype "passive"))
      (node (ref "J5") (pin "S26") (pinfunction "CHASSIS_GND3_S26") (pintype "passive"))
      (node (ref "J5") (pin "S27") (pinfunction "CHASSIS_GND3_S27") (pintype "passive"))
      (node (ref "J5") (pin "S28") (pinfunction "CHASSIS_GND3_S28") (pintype "passive"))
      (node (ref "J5") (pin "S30") (pinfunction "CHASSIS_GND3_S30") (pintype "passive"))
      (node (ref "J5") (pin "S31") (pinfunction "CHASSIS_GND3_S31") (pintype "passive"))
      (node (ref "J5") (pin "S32") (pinfunction "CHASSIS_GND3_S32") (pintype "passive"))
      (node (ref "J5") (pin "S33") (pinfunction "CHASSIS_GND3_S33") (pintype "passive"))
      (node (ref "J5") (pin "S34") (pinfunction "CHASSIS_GND3_S34") (pintype "passive"))
      (node (ref "J5") (pin "S35") (pinfunction "CHASSIS_GND3_S35") (pintype "passive"))
      (node (ref "R196") (pin "1") (pinfunction "1_1") (pintype "passive"))
      (node (ref "R197") (pin "1") (pinfunction "1_1") (pintype "passive"))
      (node (ref "R198") (pin "1") (pinfunction "1_1") (pintype "passive"))
      (node (ref "R201") (pin "1") (pinfunction "1_1") (pintype "passive"))
      (node (ref "R202") (pin "1") (pinfunction "1_1") (pintype "passive"))
      (node (ref "R203") (pin "1") (pinfunction "1_1") (pintype "passive"))
    )
    (net (code "18") (name "P3V3") (class "Default")
      (node (ref "C192") (pin "1") (pinfunction "1_1") (pintype "passive"))
      (node (ref "C193") (pin "2") (pinfunction "2_2") (pintype "passive"))
      (node (ref "C194") (pin "1") (pinfunction "1_1") (pintype "passive"))
      (node (ref "C198") (pin "1") (pinfunction "1_1") (pintype "passive"))
      (node (ref "C199") (pin "2") (pinfunction "2_2") (pintype "passive"))
      (node (ref "C200") (pin "1") (pinfunction "1_1") (pintype "passive"))
      (node (ref "C212") (pin "1") (pinfunction "1_1") (pintype "passive"))
      (node (ref "C215") (pin "2") (pinfunction "2_2") (pintype "passive"))
      (node (ref "C216") (pin "1") (pinfunction "1_1") (pintype "passive"))
      (node (ref "C220") (pin "1") (pinfunction "1_1") (pintype "passive"))
      (node (ref "C221") (pin "2") (pinfunction "2_2") (pintype "passive"))
      (node (ref "C222") (pin "1") (pinfunction "1_1") (pintype "passive"))
      (node (ref "FB6") (pin "1") (pinfunction "1_1") (pintype "passive"))
      (node (ref "FB7") (pin "1") (pinfunction "1_1") (pintype "passive"))
      (node (ref "FB8") (pin "1") (pinfunction "1_1") (pintype "passive"))
      (node (ref "FB9") (pin "1") (pinfunction "1_1") (pintype "passive"))
      (node (ref "R133") (pin "1") (pinfunction "1_1") (pintype "passive"))
      (node (ref "R134") (pin "1") (pinfunction "1_1") (pintype "passive"))
      (node (ref "R136") (pin "1") (pinfunction "1_1") (pintype "passive"))
      (node (ref "R137") (pin "1") (pinfunction "1_1") (pintype "passive"))
      (node (ref "R138") (pin "1") (pinfunction "1_1") (pintype "passive"))
      (node (ref "R140") (pin "1") (pinfunction "1_1") (pintype "passive"))
      (node (ref "R141") (pin "1") (pinfunction "1_1") (pintype "passive"))
      (node (ref "R148") (pin "1") (pinfunction "1_1") (pintype "passive"))
      (node (ref "R149") (pin "1") (pinfunction "1_1") (pintype "passive"))
      (node (ref "R150") (pin "1") (pinfunction "1_1") (pintype "passive"))
      (node (ref "R151") (pin "1") (pinfunction "1_1") (pintype "passive"))
      (node (ref "R152") (pin "1") (pinfunction "1_1") (pintype "passive"))
      (node (ref "R153") (pin "1") (pinfunction "1_1") (pintype "passive"))
      (node (ref "R154") (pin "1") (pinfunction "1_1") (pintype "passive"))
      (node (ref "R194") (pin "2") (pinfunction "2_2") (pintype "passive"))
      (node (ref "R195") (pin "2") (pinfunction "2_2") (pintype "passive"))
      (node (ref "R199") (pin "2") (pinfunction "2_2") (pintype "passive"))
      (node (ref "R200") (pin "2") (pinfunction "2_2") (pintype "passive"))
    )
    (net (code "19") (name "SFP3_FAULT") (class "Default")
      (node (ref "J5") (pin "P3_2") (pinfunction "P3_2_P3_2") (pintype "passive"))
      (node (ref "R134") (pin "2") (pinfunction "2_2") (pintype "passive"))
    )
    (net (code "20") (name "SFP3_LOS") (class "Default")
      (node (ref "J5") (pin "P3_8") (pinfunction "P3_8_P3_8") (pintype "passive"))
      (node (ref "R141") (pin "2") (pinfunction "2_2") (pintype "passive"))
    )
    (net (code "21") (name "SFP3_MOD_ABS") (class "Default")
      (node (ref "J5") (pin "P3_6") (pinfunction "P3_6_P3_6") (pintype "passive"))
      (node (ref "R138") (pin "2") (pinfunction "2_2") (pintype "passive"))
    )
    (net (code "22") (name "SFP3_RATE_SELECT") (class "Default")
      (node (ref "J5") (pin "P3_7") (pinfunction "P3_7_P3_7") (pintype "passive"))
      (node (ref "R140") (pin "2") (pinfunction "2_2") (pintype "passive"))
    )
    (net (code "23") (name "SFP3_SCL") (class "Default")
      (node (ref "J5") (pin "P3_5") (pinfunction "P3_5_P3_5") (pintype "passive"))
      (node (ref "R137") (pin "2") (pinfunction "2_2") (pintype "passive"))
    )
    (net (code "24") (name "SFP3_SDA") (class "Default")
      (node (ref "J5") (pin "P3_4") (pinfunction "P3_4_P3_4") (pintype "passive"))
      (node (ref "R136") (pin "2") (pinfunction "2_2") (pintype "passive"))
    )
    (net (code "25") (name "SFP3_TXDISABLE") (class "Default")
      (node (ref "J5") (pin "P3_3") (pinfunction "P3_3_P3_3") (pintype "passive"))
      (node (ref "R133") (pin "2") (pinfunction "2_2") (pintype "passive"))
      (node (ref "R196") (pin "2") (pinfunction "2_2") (pintype "passive"))
    )
    (net (code "26") (name "SFP3_VCCR") (class "Default")
      (node (ref "C201") (pin "1") (pinfunction "1_1") (pintype "passive"))
      (node (ref "C202") (pin "2") (pinfunction "2_2") (pintype "passive"))
      (node (ref "C203") (pin "1") (pinfunction "1_1") (pintype "passive"))
      (node (ref "FB7") (pin "2") (pinfunction "2_2") (pintype "passive"))
      (node (ref "J5") (pin "P3_15") (pinfunction "P3_15_P3_15") (pintype "passive"))
    )
    (net (code "27") (name "SFP3_VCCT") (class "Default")
      (node (ref "C195") (pin "1") (pinfunction "1_1") (pintype "passive"))
      (node (ref "C196") (pin "2") (pinfunction "2_2") (pintype "passive"))
      (node (ref "C197") (pin "1") (pinfunction "1_1") (pintype "passive"))
      (node (ref "FB6") (pin "2") (pinfunction "2_2") (pintype "passive"))
      (node (ref "J5") (pin "P3_16") (pinfunction "P3_16_P3_16") (pintype "passive"))
    )
    (net (code "28") (name "SFP4_FAULT") (class "Default")
      (node (ref "J5") (pin "P4_2") (pinfunction "P4_2_P4_2") (pintype "passive"))
      (node (ref "R149") (pin "2") (pinfunction "2_2") (pintype "passive"))
    )
    (net (code "29") (name "SFP4_LOS") (class "Default")
      (node (ref "J5") (pin "P4_8") (pinfunction "P4_8_P4_8") (pintype "passive"))
      (node (ref "R154") (pin "2") (pinfunction "2_2") (pintype "passive"))
    )
    (net (code "30") (name "SFP4_MOD_ABS") (class "Default")
      (node (ref "J5") (pin "P4_6") (pinfunction "P4_6_P4_6") (pintype "passive"))
      (node (ref "R152") (pin "2") (pinfunction "2_2") (pintype "passive"))
    )
    (net (code "31") (name "SFP4_RATE_SELECT") (class "Default")
      (node (ref "J5") (pin "P4_7") (pinfunction "P4_7_P4_7") (pintype "passive"))
      (node (ref "R153") (pin "2") (pinfunction "2_2") (pintype "passive"))
    )
    (net (code "32") (name "SFP4_SCL") (class "Default")
      (node (ref "J5") (pin "P4_5") (pinfunction "P4_5_P4_5") (pintype "passive"))
      (node (ref "R151") (pin "2") (pinfunction "2_2") (pintype "passive"))
    )
    (net (code "33") (name "SFP4_SDA") (class "Default")
      (node (ref "J5") (pin "P4_4") (pinfunction "P4_4_P4_4") (pintype "passive"))
      (node (ref "R150") (pin "2") (pinfunction "2_2") (pintype "passive"))
    )
    (net (code "34") (name "SFP4_TXDISABLE") (class "Default")
      (node (ref "J5") (pin "P4_3") (pinfunction "P4_3_P4_3") (pintype "passive"))
      (node (ref "R148") (pin "2") (pinfunction "2_2") (pintype "passive"))
      (node (ref "R201") (pin "2") (pinfunction "2_2") (pintype "passive"))
    )
    (net (code "35") (name "SFP4_VCCR") (class "Default")
      (node (ref "C223") (pin "1") (pinfunction "1_1") (pintype "passive"))
      (node (ref "C224") (pin "2") (pinfunction "2_2") (pintype "passive"))
      (node (ref "C225") (pin "1") (pinfunction "1_1") (pintype "passive"))
      (node (ref "FB9") (pin "2") (pinfunction "2_2") (pintype "passive"))
      (node (ref "J5") (pin "P4_15") (pinfunction "P4_15_P4_15") (pintype "passive"))
    )
    (net (code "36") (name "SFP4_VCCT") (class "Default")
      (node (ref "C217") (pin "1") (pinfunction "1_1") (pintype "passive"))
      (node (ref "C218") (pin "2") (pinfunction "2_2") (pintype "passive"))
      (node (ref "C219") (pin "1") (pinfunction "1_1") (pintype "passive"))
      (node (ref "FB8") (pin "2") (pinfunction "2_2") (pintype "passive"))
      (node (ref "J5") (pin "P4_16") (pinfunction "P4_16_P4_16") (pintype "passive"))
    )
    (net (code "37") (name "unconnected-(J7-Pad1)") (class "Default")
      (node (ref "J7") (pin "1") (pinfunction "1_1") (pintype "passive"))
    )
    (net (code "38") (name "unconnected-(J7-Pad2)") (class "Default")
      (node (ref "J7") (pin "2") (pinfunction "2_2") (pintype "passive"))
    )
    (net (code "39") (name "unconnected-(J7-Pad3)") (class "Default")
      (node (ref "J7") (pin "3") (pinfunction "3_3") (pintype "passive"))
    )
    (net (code "40") (name "unconnected-(J7-Pad4)") (class "Default")
      (node (ref "J7") (pin "4") (pinfunction "4_4") (pintype "passive"))
    )
    (net (code "41") (name "unconnected-(J7-Pad5)") (class "Default")
      (node (ref "J7") (pin "5") (pinfunction "5_5") (pintype "passive"))
    )
    (net (code "42") (name "unconnected-(J7-Pad6)") (class "Default")
      (node (ref "J7") (pin "6") (pinfunction "6_6") (pintype "passive"))
    )
    (net (code "43") (name "unconnected-(J7-Pad7)") (class "Default")
      (node (ref "J7") (pin "7") (pinfunction "7_7") (pintype "passive"))
    )
    (net (code "44") (name "unconnected-(J7-Pad8)") (class "Default")
      (node (ref "J7") (pin "8") (pinfunction "8_8") (pintype "passive"))
    )
    (net (code "45") (name "unconnected-(J7-Pad9)") (class "Default")
      (node (ref "J7") (pin "9") (pinfunction "9_9") (pintype "passive"))
    )
    (net (code "46") (name "unconnected-(J7-Pad10)") (class "Default")
      (node (ref "J7") (pin "10") (pinfunction "10_10") (pintype "passive"))
    )
    (net (code "47") (name "unconnected-(J7-Pad11)") (class "Default")
      (node (ref "J7") (pin "11") (pinfunction "11_11") (pintype "passive"))
    )
    (net (code "48") (name "unconnected-(J7-Pad12)") (class "Default")
      (node (ref "J7") (pin "12") (pinfunction "12_12") (pintype "passive"))
    )
    (net (code "49") (name "unconnected-(J7-Pad13)") (class "Default")
      (node (ref "J7") (pin "13") (pinfunction "13_13") (pintype "passive"))
    )
    (net (code "50") (name "unconnected-(J7-Pad14)") (class "Default")
      (node (ref "J7") (pin "14") (pinfunction "14_14") (pintype "passive"))
    )
    (net (code "51") (name "unconnected-(J7-Pad15)") (class "Default")
      (node (ref "J7") (pin "15") (pinfunction "15_15") (pintype "passive"))
    )
    (net (code "52") (name "unconnected-(J7-Pad16)") (class "Default")
      (node (ref "J7") (pin "16") (pinfunction "16_16") (pintype "passive"))
    )
    (net (code "53") (name "unconnected-(J7-Pad17)") (class "Default")
      (node (ref "J7") (pin "17") (pinfunction "17_17") (pintype "passive"))
    )
    (net (code "54") (name "unconnected-(J7-Pad18)") (class "Default")
      (node (ref "J7") (pin "18") (pinfunction "18_18") (pintype "passive"))
    )
    (net (code "55") (name "unconnected-(J7-Pad19)") (class "Default")
      (node (ref "J7") (pin "19") (pinfunction "19_19") (pintype "passive"))
    )
    (net (code "56") (name "unconnected-(J7-Pad20)") (class "Default")
      (node (ref "J7") (pin "20") (pinfunction "20_20") (pintype "passive"))
    )
    (net (code "57") (name "unconnected-(J8-Pad1)") (class "Default")
      (node (ref "J8") (pin "1") (pinfunction "1_1") (pintype "passive"))
    )
    (net (code "58") (name "unconnected-(J8-Pad2)") (class "Default")
      (node (ref "J8") (pin "2") (pinfunction "2_2") (pintype "passive"))
    )
    (net (code "59") (name "unconnected-(J8-Pad3)") (class "Default")
      (node (ref "J8") (pin "3") (pinfunction "3_3") (pintype "passive"))
    )
    (net (code "60") (name "unconnected-(J8-Pad4)") (class "Default")
      (node (ref "J8") (pin "4") (pinfunction "4_4") (pintype "passive"))
    )
    (net (code "61") (name "unconnected-(J8-Pad5)") (class "Default")
      (node (ref "J8") (pin "5") (pinfunction "5_5") (pintype "passive"))
    )
    (net (code "62") (name "unconnected-(J8-Pad6)") (class "Default")
      (node (ref "J8") (pin "6") (pinfunction "6_6") (pintype "passive"))
    )
    (net (code "63") (name "unconnected-(J8-Pad7)") (class "Default")
      (node (ref "J8") (pin "7") (pinfunction "7_7") (pintype "passive"))
    )
    (net (code "64") (name "unconnected-(J8-Pad8)") (class "Default")
      (node (ref "J8") (pin "8") (pinfunction "8_8") (pintype "passive"))
    )
    (net (code "65") (name "unconnected-(J8-Pad9)") (class "Default")
      (node (ref "J8") (pin "9") (pinfunction "9_9") (pintype "passive"))
    )
    (net (code "66") (name "unconnected-(J8-Pad10)") (class "Default")
      (node (ref "J8") (pin "10") (pinfunction "10_10") (pintype "passive"))
    )
    (net (code "67") (name "unconnected-(J8-Pad11)") (class "Default")
      (node (ref "J8") (pin "11") (pinfunction "11_11") (pintype "passive"))
    )
    (net (code "68") (name "unconnected-(J8-Pad12)") (class "Default")
      (node (ref "J8") (pin "12") (pinfunction "12_12") (pintype "passive"))
    )
    (net (code "69") (name "unconnected-(J8-Pad13)") (class "Default")
      (node (ref "J8") (pin "13") (pinfunction "13_13") (pintype "passive"))
    )
    (net (code "70") (name "unconnected-(J8-Pad14)") (class "Default")
      (node (ref "J8") (pin "14") (pinfunction "14_14") (pintype "passive"))
    )
    (net (code "71") (name "unconnected-(J8-Pad15)") (class "Default")
      (node (ref "J8") (pin "15") (pinfunction "15_15") (pintype "passive"))
    )
    (net (code "72") (name "unconnected-(J8-Pad16)") (class "Default")
      (node (ref "J8") (pin "16") (pinfunction "16_16") (pintype "passive"))
    )
    (net (code "73") (name "unconnected-(J8-Pad17)") (class "Default")
      (node (ref "J8") (pin "17") (pinfunction "17_17") (pintype "passive"))
    )
    (net (code "74") (name "unconnected-(J8-Pad18)") (class "Default")
      (node (ref "J8") (pin "18") (pinfunction "18_18") (pintype "passive"))
    )
    (net (code "75") (name "unconnected-(J8-Pad19)") (class "Default")
      (node (ref "J8") (pin "19") (pinfunction "19_19") (pintype "passive"))
    )
    (net (code "76") (name "unconnected-(J8-Pad20)") (class "Default")
      (node (ref "J8") (pin "20") (pinfunction "20_20") (pintype "passive"))
    )
  )
)
